# MB1019.net
KiCad netlist of a schematic drawn in Altium Designer
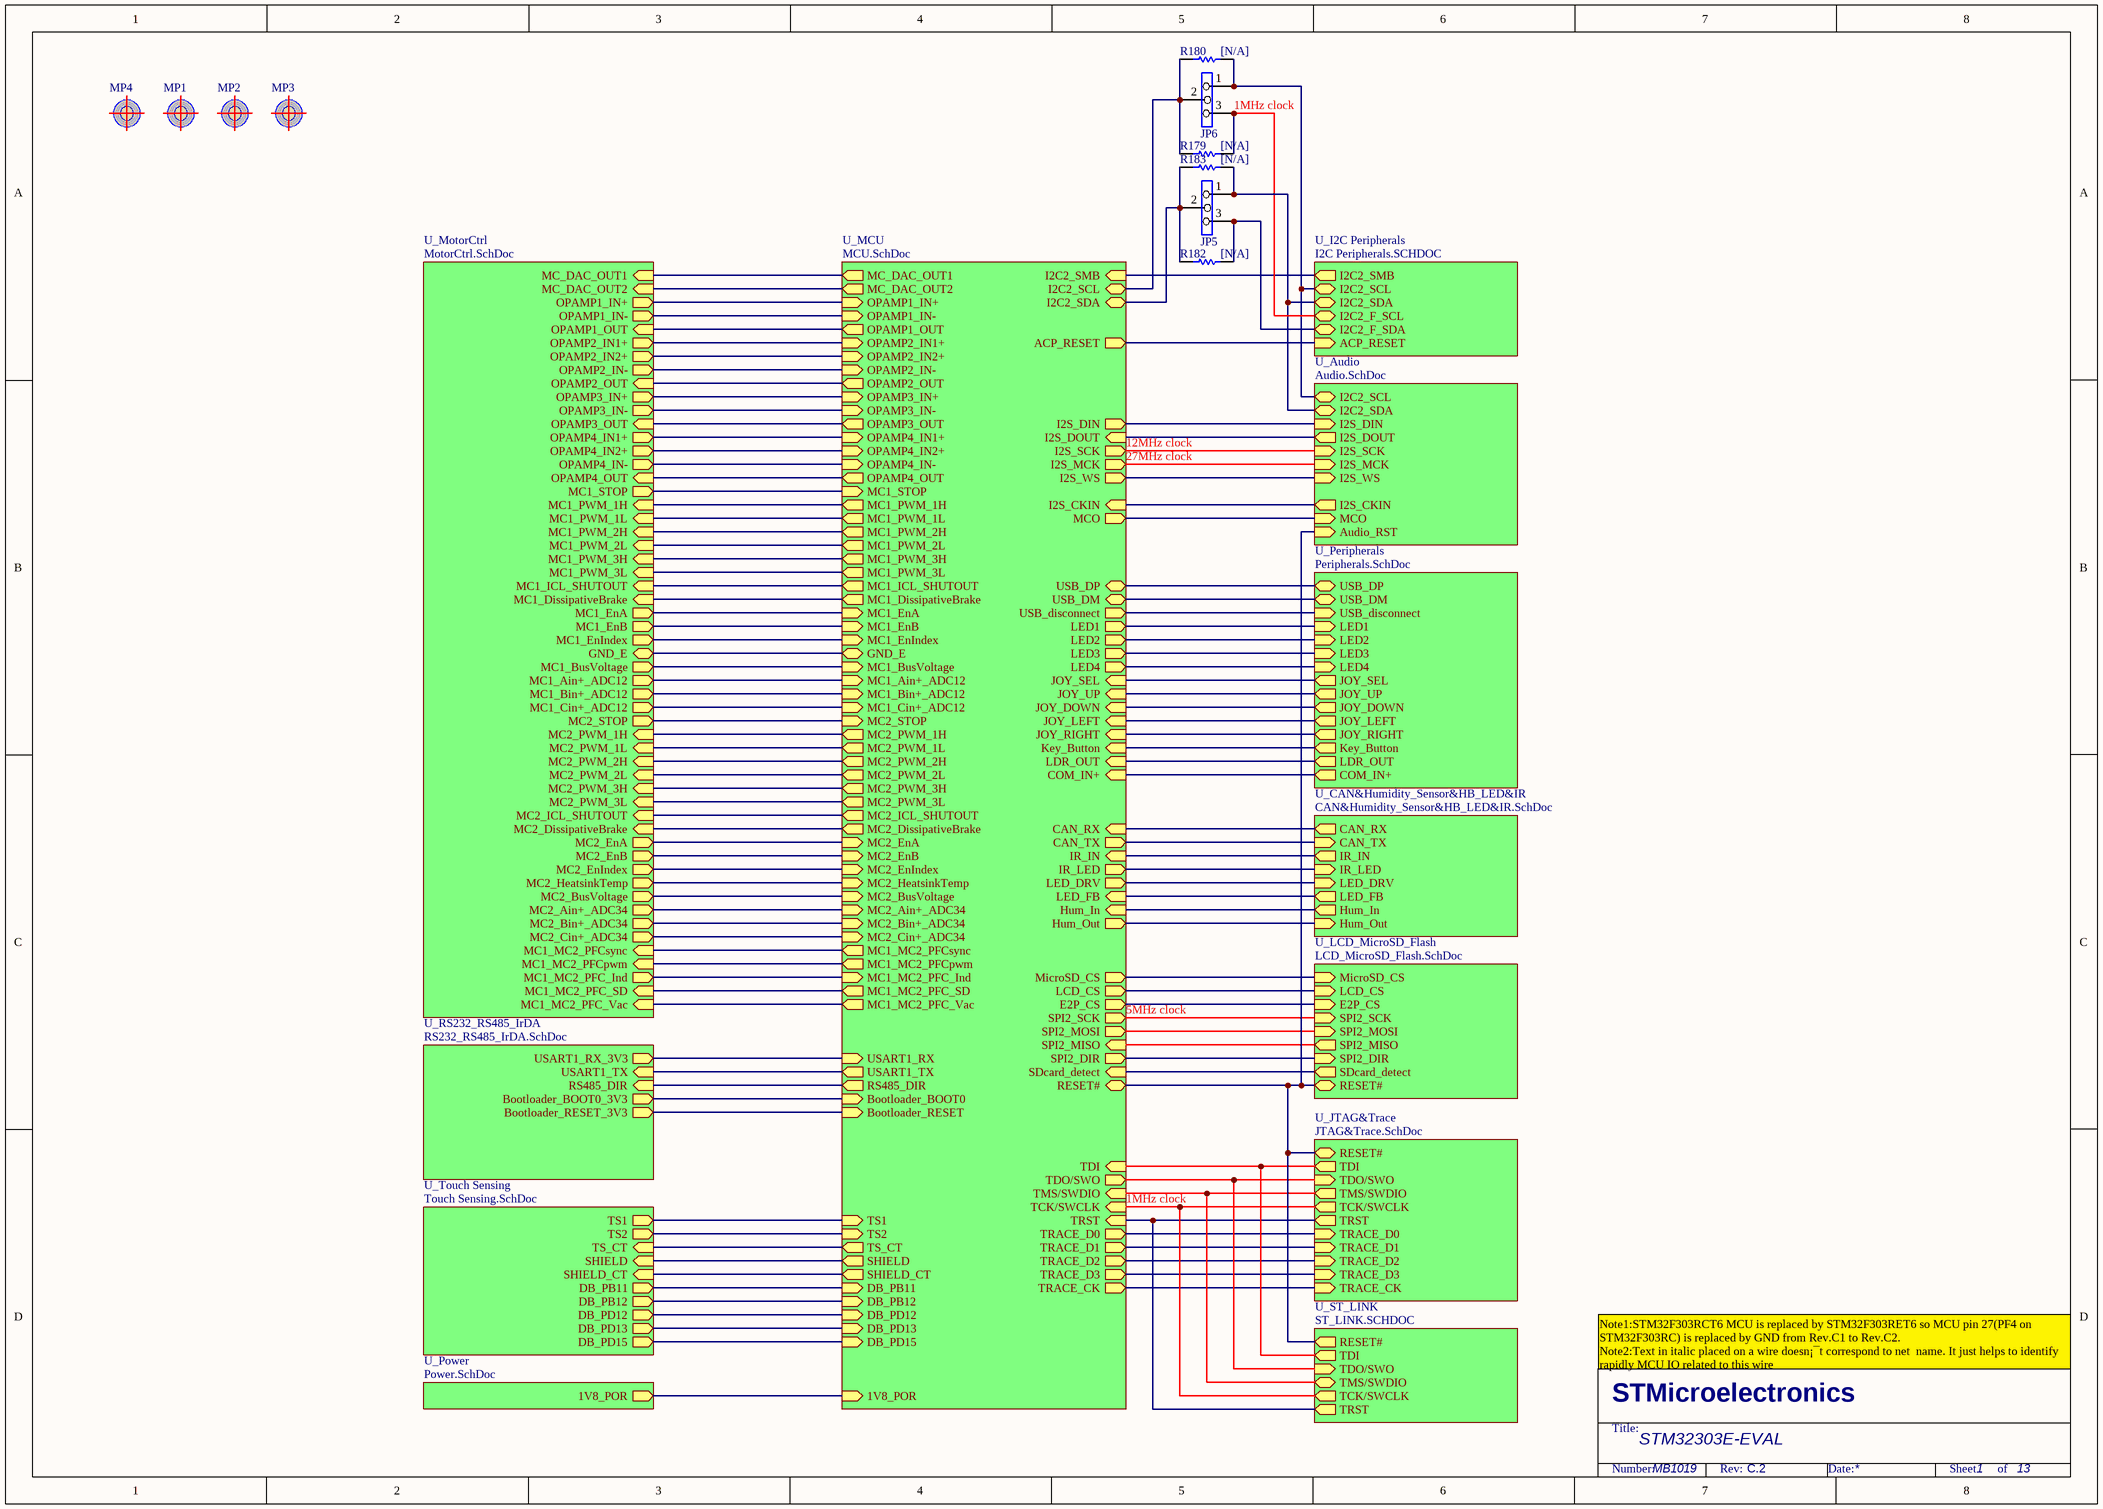
[diagram p0: MB1019.SchDoc]

(export (version "E")
  (design (tool "Eeschema 10.0.6"))
  (components
    (comp (ref "JP5") (value "~") (footprint "SIP3") (libsource (lib "STR910_SCHLIB") (part "Jumper3")))
    (comp (ref "JP6") (value "~") (footprint "SIP3") (libsource (lib "STR910_SCHLIB") (part "Jumper3")))
    (comp (ref "MP1") (value "~") (footprint "markpoint_1.0") (libsource (lib "*") (part "MARKPOINT")))
    (comp (ref "MP2") (value "~") (footprint "markpoint_1.0") (libsource (lib "*") (part "MARKPOINT")))
    (comp (ref "MP3") (value "~") (footprint "markpoint_1.0") (libsource (lib "*") (part "MARKPOINT")))
    (comp (ref "MP4") (value "~") (footprint "markpoint_1.0") (libsource (lib "*") (part "MARKPOINT")))
    (comp (ref "R179")
      (value "[N/A]")
      (footprint "0603R")
      (description "Resistor")
      (fields (field (name "PUBLISHER") "Altium Limited"))
      (libsource (lib "Miscellaneous Devices") (part "Res1"))
    )
    (comp (ref "R180")
      (value "[N/A]")
      (footprint "0603R")
      (description "Resistor")
      (fields (field (name "PUBLISHER") "Altium Limited"))
      (libsource (lib "Miscellaneous Devices") (part "Res1"))
    )
    (comp (ref "R182")
      (value "[N/A]")
      (footprint "0603R")
      (description "Resistor")
      (fields (field (name "PUBLISHER") "Altium Limited"))
      (libsource (lib "Miscellaneous Devices") (part "Res1"))
    )
    (comp (ref "R183")
      (value "[N/A]")
      (footprint "0603R")
      (description "Resistor")
      (fields (field (name "PUBLISHER") "Altium Limited"))
      (libsource (lib "Miscellaneous Devices") (part "Res1"))
    )
  )
  (nets
    (net (code "17") (name "/I2C2_F_SCL") (class "Default")
      (node (ref "JP6") (pin "3") (pintype "passive"))
      (node (ref "R179") (pin "1") (pinfunction "1_1") (pintype "passive"))
    )
    (net (code "18") (name "/I2C2_F_SDA") (class "Default")
      (node (ref "JP5") (pin "3") (pintype "passive"))
      (node (ref "R182") (pin "1") (pinfunction "1_1") (pintype "passive"))
    )
    (net (code "19") (name "/I2C2_SCL") (class "Default")
      (node (ref "JP6") (pin "1") (pintype "passive"))
      (node (ref "R180") (pin "1") (pinfunction "1_1") (pintype "passive"))
    )
    (net (code "20") (name "/I2C2_SCL_1") (class "Default")
      (node (ref "JP6") (pin "2") (pintype "passive"))
      (node (ref "R179") (pin "2") (pinfunction "2_2") (pintype "passive"))
      (node (ref "R180") (pin "2") (pinfunction "2_2") (pintype "passive"))
    )
    (net (code "21") (name "/I2C2_SDA") (class "Default")
      (node (ref "JP5") (pin "1") (pintype "passive"))
      (node (ref "R183") (pin "1") (pinfunction "1_1") (pintype "passive"))
    )
    (net (code "22") (name "/I2C2_SDA_1") (class "Default")
      (node (ref "JP5") (pin "2") (pintype "passive"))
      (node (ref "R182") (pin "2") (pinfunction "2_2") (pintype "passive"))
      (node (ref "R183") (pin "2") (pinfunction "2_2") (pintype "passive"))
    )
  )
)
